# PRTF02.net
KiCad netlist of a schematic drawn in EAGLE
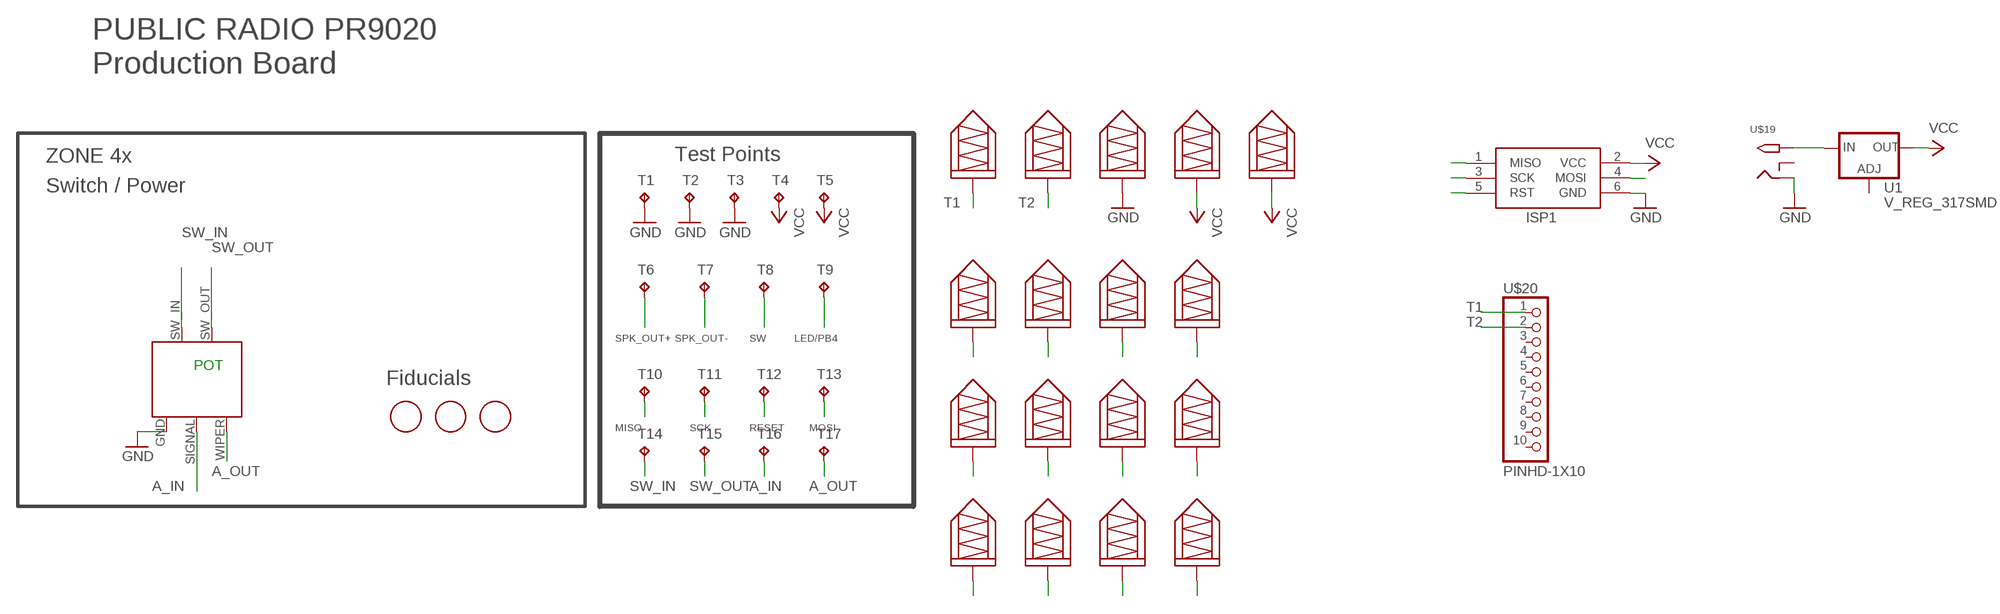
[diagram p0: schematic, sheet 1]

(export (version "E")
  (design (tool "Eeschema 10.0.6"))
  (components
    (comp (ref "ISP1")
      (value "AVRISP-6")
      (footprint "eagle-import:AVRISP")
      (libsource (lib "eagle-import") (part "AVRISP-6"))
    )
    (comp (ref "MARK1")
      (value "FIDUCIAL")
      (footprint "eagle-import:FIDUCIAL_1MM")
      (libsource (lib "eagle-import") (part "FIDUCIAL"))
    )
    (comp (ref "MARK2")
      (value "FIDUCIAL")
      (footprint "eagle-import:FIDUCIAL_1MM")
      (libsource (lib "eagle-import") (part "FIDUCIAL"))
    )
    (comp (ref "MARK3")
      (value "FIDUCIAL")
      (footprint "eagle-import:FIDUCIAL_1MM")
      (libsource (lib "eagle-import") (part "FIDUCIAL"))
    )
    (comp (ref "R1")
      (value "RV170SF_TAIWANA_POT_SW")
      (footprint "eagle-import:RV170SF_SW_POT")
      (fields (field (name "MFG_PN") "RV170SF-43-20F-A10K - supplied by CL Labs"))
      (libsource (lib "eagle-import") (part "RV170SF_TAIWANA_POT_SW"))
    )
    (comp (ref "T1")
      (value "TPTP20R")
      (footprint "eagle-import:TP20R")
      (libsource (lib "eagle-import") (part "TPTP20R"))
    )
    (comp (ref "T2")
      (value "TPTP20R")
      (footprint "eagle-import:TP20R")
      (libsource (lib "eagle-import") (part "TPTP20R"))
    )
    (comp (ref "T3")
      (value "TPTP20R")
      (footprint "eagle-import:TP20R")
      (libsource (lib "eagle-import") (part "TPTP20R"))
    )
    (comp (ref "T4")
      (value "TPTP20R")
      (footprint "eagle-import:TP20R")
      (libsource (lib "eagle-import") (part "TPTP20R"))
    )
    (comp (ref "T5")
      (value "TPTP20R")
      (footprint "eagle-import:TP20R")
      (libsource (lib "eagle-import") (part "TPTP20R"))
    )
    (comp (ref "T6")
      (value "TPTP20R")
      (footprint "eagle-import:TP20R")
      (libsource (lib "eagle-import") (part "TPTP20R"))
    )
    (comp (ref "T7")
      (value "TPTP20R")
      (footprint "eagle-import:TP20R")
      (libsource (lib "eagle-import") (part "TPTP20R"))
    )
    (comp (ref "T8")
      (value "TPTP20R")
      (footprint "eagle-import:TP20R")
      (libsource (lib "eagle-import") (part "TPTP20R"))
    )
    (comp (ref "T9")
      (value "TPTP20R")
      (footprint "eagle-import:TP20R")
      (libsource (lib "eagle-import") (part "TPTP20R"))
    )
    (comp (ref "T10")
      (value "TPTP20R")
      (footprint "eagle-import:TP20R")
      (libsource (lib "eagle-import") (part "TPTP20R"))
    )
    (comp (ref "T11")
      (value "TPTP20R")
      (footprint "eagle-import:TP20R")
      (libsource (lib "eagle-import") (part "TPTP20R"))
    )
    (comp (ref "T12")
      (value "TPTP20R")
      (footprint "eagle-import:TP20R")
      (libsource (lib "eagle-import") (part "TPTP20R"))
    )
    (comp (ref "T13")
      (value "TPTP20R")
      (footprint "eagle-import:TP20R")
      (libsource (lib "eagle-import") (part "TPTP20R"))
    )
    (comp (ref "T14")
      (value "TPTP20R")
      (footprint "eagle-import:TP20R")
      (libsource (lib "eagle-import") (part "TPTP20R"))
    )
    (comp (ref "T15")
      (value "TPTP20R")
      (footprint "eagle-import:TP20R")
      (libsource (lib "eagle-import") (part "TPTP20R"))
    )
    (comp (ref "T16")
      (value "TPTP20R")
      (footprint "eagle-import:TP20R")
      (libsource (lib "eagle-import") (part "TPTP20R"))
    )
    (comp (ref "T17")
      (value "TPTP20R")
      (footprint "eagle-import:TP20R")
      (libsource (lib "eagle-import") (part "TPTP20R"))
    )
    (comp (ref "U$2")
      (value "0908MILL_MAX_SPRINGPIN")
      (footprint "eagle-import:0908MILL_MAX_SPRINGPIN")
      (libsource (lib "eagle-import") (part "0908MILL_MAX_SPRINGPIN"))
    )
    (comp (ref "U$3")
      (value "0908MILL_MAX_SPRINGPIN")
      (footprint "eagle-import:0908MILL_MAX_SPRINGPIN")
      (libsource (lib "eagle-import") (part "0908MILL_MAX_SPRINGPIN"))
    )
    (comp (ref "U$4")
      (value "0908MILL_MAX_SPRINGPIN")
      (footprint "eagle-import:0908MILL_MAX_SPRINGPIN")
      (libsource (lib "eagle-import") (part "0908MILL_MAX_SPRINGPIN"))
    )
    (comp (ref "U$5")
      (value "0908MILL_MAX_SPRINGPIN")
      (footprint "eagle-import:0908MILL_MAX_SPRINGPIN")
      (libsource (lib "eagle-import") (part "0908MILL_MAX_SPRINGPIN"))
    )
    (comp (ref "U$6")
      (value "0908MILL_MAX_SPRINGPIN")
      (footprint "eagle-import:0908MILL_MAX_SPRINGPIN")
      (libsource (lib "eagle-import") (part "0908MILL_MAX_SPRINGPIN"))
    )
    (comp (ref "U$7")
      (value "0908MILL_MAX_SPRINGPIN")
      (footprint "eagle-import:0908MILL_MAX_SPRINGPIN")
      (libsource (lib "eagle-import") (part "0908MILL_MAX_SPRINGPIN"))
    )
    (comp (ref "U$8")
      (value "0908MILL_MAX_SPRINGPIN")
      (footprint "eagle-import:0908MILL_MAX_SPRINGPIN")
      (libsource (lib "eagle-import") (part "0908MILL_MAX_SPRINGPIN"))
    )
    (comp (ref "U$9")
      (value "0908MILL_MAX_SPRINGPIN")
      (footprint "eagle-import:0908MILL_MAX_SPRINGPIN")
      (libsource (lib "eagle-import") (part "0908MILL_MAX_SPRINGPIN"))
    )
    (comp (ref "U$10")
      (value "0908MILL_MAX_SPRINGPIN")
      (footprint "eagle-import:0908MILL_MAX_SPRINGPIN")
      (libsource (lib "eagle-import") (part "0908MILL_MAX_SPRINGPIN"))
    )
    (comp (ref "U$11")
      (value "0908MILL_MAX_SPRINGPIN")
      (footprint "eagle-import:0908MILL_MAX_SPRINGPIN")
      (libsource (lib "eagle-import") (part "0908MILL_MAX_SPRINGPIN"))
    )
    (comp (ref "U$12")
      (value "0908MILL_MAX_SPRINGPIN")
      (footprint "eagle-import:0908MILL_MAX_SPRINGPIN")
      (libsource (lib "eagle-import") (part "0908MILL_MAX_SPRINGPIN"))
    )
    (comp (ref "U$13")
      (value "0908MILL_MAX_SPRINGPIN")
      (footprint "eagle-import:0908MILL_MAX_SPRINGPIN")
      (libsource (lib "eagle-import") (part "0908MILL_MAX_SPRINGPIN"))
    )
    (comp (ref "U$14")
      (value "0908MILL_MAX_SPRINGPIN")
      (footprint "eagle-import:0908MILL_MAX_SPRINGPIN")
      (libsource (lib "eagle-import") (part "0908MILL_MAX_SPRINGPIN"))
    )
    (comp (ref "U$15")
      (value "0908MILL_MAX_SPRINGPIN")
      (footprint "eagle-import:0908MILL_MAX_SPRINGPIN")
      (libsource (lib "eagle-import") (part "0908MILL_MAX_SPRINGPIN"))
    )
    (comp (ref "U$16")
      (value "0908MILL_MAX_SPRINGPIN")
      (footprint "eagle-import:0908MILL_MAX_SPRINGPIN")
      (libsource (lib "eagle-import") (part "0908MILL_MAX_SPRINGPIN"))
    )
    (comp (ref "U$17")
      (value "0908MILL_MAX_SPRINGPIN")
      (footprint "eagle-import:0908MILL_MAX_SPRINGPIN")
      (libsource (lib "eagle-import") (part "0908MILL_MAX_SPRINGPIN"))
    )
    (comp (ref "U$18")
      (value "0908MILL_MAX_SPRINGPIN")
      (footprint "eagle-import:0908MILL_MAX_SPRINGPIN")
      (libsource (lib "eagle-import") (part "0908MILL_MAX_SPRINGPIN"))
    )
    (comp (ref "U$19")
      (value "2.1MMJACKTHM")
      (footprint "eagle-import:PJ-102A")
      (libsource (lib "eagle-import") (part "2.1MMJACKTHM"))
    )
    (comp (ref "U$20")
      (value "PINHD-1X10")
      (footprint "eagle-import:1X10-BIG")
      (libsource (lib "eagle-import") (part "PINHD-1X10"))
    )
    (comp (ref "U1")
      (value "V_REG_317SMD")
      (footprint "eagle-import:SOT223")
      (libsource (lib "eagle-import") (part "V_REG_317SMD"))
    )
  )
  (nets
    (net (code "1") (name "/A_IN") (class "Default")
      (node (ref "R1") (pin "SIGNAL") (pinfunction "SIGNAL_SIGNAL") (pintype "bidirectional"))
      (node (ref "T16") (pin "TP") (pinfunction "TP_TP") (pintype "input"))
      (node (ref "U$17") (pin "P$1") (pinfunction "P$1_P$1") (pintype "bidirectional"))
    )
    (net (code "2") (name "/A_OUT") (class "Default")
      (node (ref "R1") (pin "WIPER") (pinfunction "WIPER_WIPER") (pintype "bidirectional"))
      (node (ref "T17") (pin "TP") (pinfunction "TP_TP") (pintype "input"))
      (node (ref "U$18") (pin "P$1") (pinfunction "P$1_P$1") (pintype "bidirectional"))
    )
    (net (code "3") (name "/LED{slash}PB4") (class "Default")
      (node (ref "T9") (pin "TP") (pinfunction "TP_TP") (pintype "input"))
      (node (ref "U$10") (pin "P$1") (pinfunction "P$1_P$1") (pintype "bidirectional"))
    )
    (net (code "4") (name "/MISO") (class "Default")
      (node (ref "ISP1") (pin "1") (pinfunction "MISO_1") (pintype "input"))
      (node (ref "U$11") (pin "P$1") (pinfunction "P$1_P$1") (pintype "bidirectional"))
    )
    (net (code "5") (name "/MOSI") (class "Default")
      (node (ref "ISP1") (pin "4") (pinfunction "MOSI_4") (pintype "output"))
      (node (ref "U$14") (pin "P$1") (pinfunction "P$1_P$1") (pintype "bidirectional"))
    )
    (net (code "6") (name "/RESET") (class "Default")
      (node (ref "T12") (pin "TP") (pinfunction "TP_TP") (pintype "input"))
      (node (ref "U$13") (pin "P$1") (pinfunction "P$1_P$1") (pintype "bidirectional"))
    )
    (net (code "7") (name "/SCK") (class "Default")
      (node (ref "ISP1") (pin "3") (pinfunction "SCK_3") (pintype "output"))
      (node (ref "U$12") (pin "P$1") (pinfunction "P$1_P$1") (pintype "bidirectional"))
    )
    (net (code "8") (name "/SPK_OUT+") (class "Default")
      (node (ref "T6") (pin "TP") (pinfunction "TP_TP") (pintype "input"))
      (node (ref "U$7") (pin "P$1") (pinfunction "P$1_P$1") (pintype "bidirectional"))
    )
    (net (code "9") (name "/SPK_OUT-") (class "Default")
      (node (ref "T7") (pin "TP") (pinfunction "TP_TP") (pintype "input"))
      (node (ref "U$8") (pin "P$1") (pinfunction "P$1_P$1") (pintype "bidirectional"))
    )
    (net (code "10") (name "/SW") (class "Default")
      (node (ref "T8") (pin "TP") (pinfunction "TP_TP") (pintype "input"))
      (node (ref "U$9") (pin "P$1") (pinfunction "P$1_P$1") (pintype "bidirectional"))
    )
    (net (code "11") (name "/SW_IN") (class "Default")
      (node (ref "R1") (pin "SW_IN") (pinfunction "SW_IN_SW_IN") (pintype "bidirectional"))
      (node (ref "T14") (pin "TP") (pinfunction "TP_TP") (pintype "input"))
      (node (ref "U$15") (pin "P$1") (pinfunction "P$1_P$1") (pintype "bidirectional"))
    )
    (net (code "12") (name "/SW_OUT") (class "Default")
      (node (ref "R1") (pin "SW_OUT") (pinfunction "SW_OUT_SW_OUT") (pintype "bidirectional"))
      (node (ref "T15") (pin "TP") (pinfunction "TP_TP") (pintype "input"))
      (node (ref "U$16") (pin "P$1") (pinfunction "P$1_P$1") (pintype "bidirectional"))
    )
    (net (code "13") (name "/T1") (class "Default")
      (node (ref "U$2") (pin "P$1") (pinfunction "P$1_P$1") (pintype "bidirectional"))
      (node (ref "U$20") (pin "1") (pinfunction "1_1") (pintype "passive"))
    )
    (net (code "14") (name "/T2") (class "Default")
      (node (ref "U$20") (pin "2") (pinfunction "2_2") (pintype "passive"))
      (node (ref "U$3") (pin "P$1") (pinfunction "P$1_P$1") (pintype "bidirectional"))
    )
    (net (code "15") (name "GND") (class "Default")
      (node (ref "ISP1") (pin "6") (pinfunction "GND_6") (pintype "power_in"))
      (node (ref "R1") (pin "GND") (pinfunction "GND_GND") (pintype "bidirectional"))
      (node (ref "T1") (pin "TP") (pinfunction "TP_TP") (pintype "input"))
      (node (ref "T2") (pin "TP") (pinfunction "TP_TP") (pintype "input"))
      (node (ref "T3") (pin "TP") (pinfunction "TP_TP") (pintype "input"))
      (node (ref "U$19") (pin "RING") (pinfunction "RING_RING") (pintype "bidirectional"))
      (node (ref "U$4") (pin "P$1") (pinfunction "P$1_P$1") (pintype "bidirectional"))
    )
    (net (code "16") (name "Net-(U1-IN)") (class "Default")
      (node (ref "U$19") (pin "TIP") (pinfunction "TIP_TIP") (pintype "bidirectional"))
      (node (ref "U1") (pin "3") (pinfunction "IN_3") (pintype "input"))
    )
    (net (code "17") (name "VCC") (class "Default")
      (node (ref "ISP1") (pin "2") (pinfunction "VCC_2") (pintype "power_in"))
      (node (ref "T4") (pin "TP") (pinfunction "TP_TP") (pintype "input"))
      (node (ref "T5") (pin "TP") (pinfunction "TP_TP") (pintype "input"))
      (node (ref "U$5") (pin "P$1") (pinfunction "P$1_P$1") (pintype "bidirectional"))
      (node (ref "U$6") (pin "P$1") (pinfunction "P$1_P$1") (pintype "bidirectional"))
      (node (ref "U1") (pin "2") (pinfunction "OUT_2") (pintype "output"))
    )
    (net (code "18") (name "unconnected-(ISP1-RST-Pad5)") (class "Default")
      (node (ref "ISP1") (pin "5") (pinfunction "RST_5") (pintype "output"))
    )
    (net (code "19") (name "unconnected-(T10-PadTP)") (class "Default")
      (node (ref "T10") (pin "TP") (pinfunction "TP_TP") (pintype "input"))
    )
    (net (code "20") (name "unconnected-(T11-PadTP)") (class "Default")
      (node (ref "T11") (pin "TP") (pinfunction "TP_TP") (pintype "input"))
    )
    (net (code "21") (name "unconnected-(T13-PadTP)") (class "Default")
      (node (ref "T13") (pin "TP") (pinfunction "TP_TP") (pintype "input"))
    )
    (net (code "22") (name "unconnected-(U$19-PadRING_SW)") (class "Default")
      (node (ref "U$19") (pin "RING_SW") (pinfunction "RING_SW_RING_SW") (pintype "bidirectional"))
    )
    (net (code "23") (name "unconnected-(U$20-Pad3)") (class "Default")
      (node (ref "U$20") (pin "3") (pinfunction "3_3") (pintype "passive"))
    )
    (net (code "24") (name "unconnected-(U$20-Pad4)") (class "Default")
      (node (ref "U$20") (pin "4") (pinfunction "4_4") (pintype "passive"))
    )
    (net (code "25") (name "unconnected-(U$20-Pad5)") (class "Default")
      (node (ref "U$20") (pin "5") (pinfunction "5_5") (pintype "passive"))
    )
    (net (code "26") (name "unconnected-(U$20-Pad6)") (class "Default")
      (node (ref "U$20") (pin "6") (pinfunction "6_6") (pintype "passive"))
    )
    (net (code "27") (name "unconnected-(U$20-Pad7)") (class "Default")
      (node (ref "U$20") (pin "7") (pinfunction "7_7") (pintype "passive"))
    )
    (net (code "28") (name "unconnected-(U$20-Pad8)") (class "Default")
      (node (ref "U$20") (pin "8") (pinfunction "8_8") (pintype "passive"))
    )
    (net (code "29") (name "unconnected-(U$20-Pad9)") (class "Default")
      (node (ref "U$20") (pin "9") (pinfunction "9_9") (pintype "passive"))
    )
    (net (code "30") (name "unconnected-(U$20-Pad10)") (class "Default")
      (node (ref "U$20") (pin "10") (pinfunction "10_10") (pintype "passive"))
    )
    (net (code "31") (name "unconnected-(U1-ADJ-Pad1)") (class "Default")
      (node (ref "U1") (pin "1") (pinfunction "ADJ_1") (pintype "input"))
    )
  )
)
